# CurrentSens.net
KiCad netlist of a schematic drawn in Altium Designer
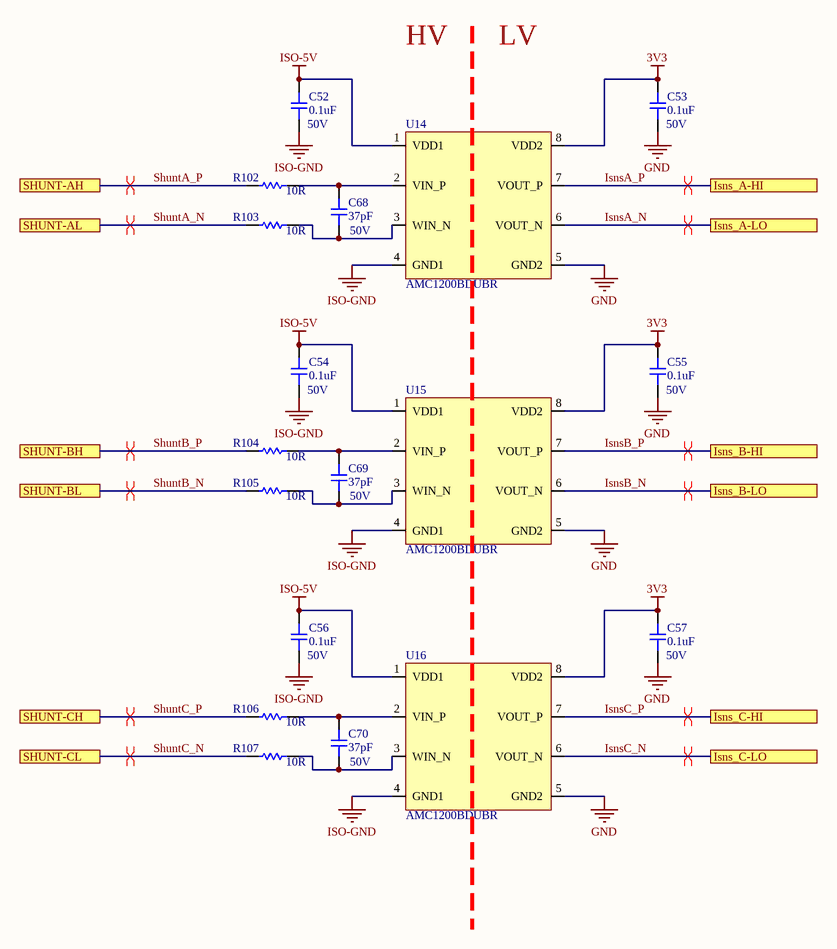
[diagram p0: CurrentSens.SchDoc]

(export (version "E")
  (design (tool "Eeschema 10.0.6"))
  (components
    (comp (ref "C52")
      (value "0.1uF")
      (footprint "CAP-0805")
      (description "CAP CER 0.1UF 50V Y5V 0805")
      (fields
        (field (name "MANUFACTURER") "KEMET")
        (field (name "MANUFACTURER PART NUMBER") "C0805C104Z5VACTU")
        (field (name "VOLTAGE") "50V")
      )
      (libsource (lib "InverterSCHLib") (part "0805-0.1uF-50V"))
    )
    (comp (ref "C53")
      (value "0.1uF")
      (footprint "CAP-0805")
      (description "CAP CER 0.1UF 50V Y5V 0805")
      (fields
        (field (name "MANUFACTURER") "KEMET")
        (field (name "MANUFACTURER PART NUMBER") "C0805C104Z5VACTU")
        (field (name "VOLTAGE") "50V")
      )
      (libsource (lib "InverterSCHLib") (part "0805-0.1uF-50V"))
    )
    (comp (ref "C54")
      (value "0.1uF")
      (footprint "CAP-0805")
      (description "CAP CER 0.1UF 50V Y5V 0805")
      (fields
        (field (name "MANUFACTURER") "KEMET")
        (field (name "MANUFACTURER PART NUMBER") "C0805C104Z5VACTU")
        (field (name "VOLTAGE") "50V")
      )
      (libsource (lib "InverterSCHLib") (part "0805-0.1uF-50V"))
    )
    (comp (ref "C55")
      (value "0.1uF")
      (footprint "CAP-0805")
      (description "CAP CER 0.1UF 50V Y5V 0805")
      (fields
        (field (name "MANUFACTURER") "KEMET")
        (field (name "MANUFACTURER PART NUMBER") "C0805C104Z5VACTU")
        (field (name "VOLTAGE") "50V")
      )
      (libsource (lib "InverterSCHLib") (part "0805-0.1uF-50V"))
    )
    (comp (ref "C56")
      (value "0.1uF")
      (footprint "CAP-0805")
      (description "CAP CER 0.1UF 50V Y5V 0805")
      (fields
        (field (name "MANUFACTURER") "KEMET")
        (field (name "MANUFACTURER PART NUMBER") "C0805C104Z5VACTU")
        (field (name "VOLTAGE RATING") "50V")
      )
      (libsource (lib "InverterSCHLib") (part "0805-0.1uF-50V"))
    )
    (comp (ref "C57")
      (value "0.1uF")
      (footprint "CAP-0805")
      (description "CAP CER 0.1UF 50V Y5V 0805")
      (fields
        (field (name "MANUFACTURER") "KEMET")
        (field (name "MANUFACTURER PART NUMBER") "C0805C104Z5VACTU")
        (field (name "VOLTAGE") "50V")
      )
      (libsource (lib "InverterSCHLib") (part "0805-0.1uF-50V"))
    )
    (comp (ref "C68")
      (value "37pF")
      (footprint "CAP-0805")
      (description "CAP CER 39PF 50V C0G/NP0 0805")
      (fields
        (field (name "MANUFACTURER") "Samsung")
        (field (name "MANUFACTURER PART NUMBER") "CL21C390JBANNNC")
        (field (name "VOLTAGE") "50V")
      )
      (libsource (lib "InverterSCHLib") (part "0805-39pF-50V"))
    )
    (comp (ref "C69")
      (value "37pF")
      (footprint "CAP-0805")
      (description "CAP CER 39PF 50V C0G/NP0 0805")
      (fields
        (field (name "MANUFACTURER") "Samsung")
        (field (name "MANUFACTURER PART NUMBER") "CL21C390JBANNNC")
        (field (name "VOLTAGE") "50V")
      )
      (libsource (lib "InverterSCHLib") (part "0805-39pF-50V"))
    )
    (comp (ref "C70")
      (value "37pF")
      (footprint "CAP-0805")
      (description "CAP CER 39PF 50V C0G/NP0 0805")
      (fields
        (field (name "MANUFACTURER") "Samsung")
        (field (name "MANUFACTURER PART NUMBER") "CL21C390JBANNNC")
        (field (name "VOLTAGE") "50V")
      )
      (libsource (lib "InverterSCHLib") (part "0805-39pF-50V"))
    )
    (comp (ref "R102")
      (value "10R")
      (footprint "RES-0603")
      (description "RES SMD 10 OHM 1% 1/10W 0603")
      (fields
        (field (name "MANUFACTURER") "Yageo")
        (field (name "MANUFACTURER PART NUMBER") "RC0603FR-0710RL")
      )
      (libsource (lib "InverterSCHLib") (part "0603-10R"))
    )
    (comp (ref "R103")
      (value "10R")
      (footprint "RES-0603")
      (description "RES SMD 10 OHM 1% 1/10W 0603")
      (fields
        (field (name "MANUFACTURER") "Yageo")
        (field (name "MANUFACTURER PART NUMBER") "RC0603FR-0710RL")
      )
      (libsource (lib "InverterSCHLib") (part "0603-10R"))
    )
    (comp (ref "R104")
      (value "10R")
      (footprint "RES-0603")
      (description "RES SMD 10 OHM 1% 1/10W 0603")
      (fields
        (field (name "MANUFACTURER") "Yageo")
        (field (name "MANUFACTURER PART NUMBER") "RC0603FR-0710RL")
      )
      (libsource (lib "InverterSCHLib") (part "0603-10R"))
    )
    (comp (ref "R105")
      (value "10R")
      (footprint "RES-0603")
      (description "RES SMD 10 OHM 1% 1/10W 0603")
      (fields
        (field (name "MANUFACTURER") "Yageo")
        (field (name "MANUFACTURER PART NUMBER") "RC0603FR-0710RL")
      )
      (libsource (lib "InverterSCHLib") (part "0603-10R"))
    )
    (comp (ref "R106")
      (value "10R")
      (footprint "RES-0603")
      (description "RES SMD 10 OHM 1% 1/10W 0603")
      (fields
        (field (name "MANUFACTURER") "Yageo")
        (field (name "MANUFACTURER PART NUMBER") "RC0603FR-0710RL")
      )
      (libsource (lib "InverterSCHLib") (part "0603-10R"))
    )
    (comp (ref "R107")
      (value "10R")
      (footprint "RES-0603")
      (description "RES SMD 10 OHM 1% 1/10W 0603")
      (fields
        (field (name "MANUFACTURER") "Yageo")
        (field (name "MANUFACTURER PART NUMBER") "RC0603FR-0710RL")
      )
      (libsource (lib "InverterSCHLib") (part "0603-10R"))
    )
    (comp (ref "U14")
      (value "AMC1200BDUBR")
      (footprint "8-SOP")
      (description "IC OPAMP ISOLATION 1 CIRC 8SOP")
      (fields (field (name "MANUFACTURER") "Texas Instruments"))
      (libsource (lib "InverterSCHLib") (part "ISO-OPAMP"))
    )
    (comp (ref "U15")
      (value "AMC1200BDUBR")
      (footprint "8-SOP")
      (description "IC OPAMP ISOLATION 1 CIRC 8SOP")
      (fields (field (name "MANUFACTURER") "Texas Instruments"))
      (libsource (lib "InverterSCHLib") (part "ISO-OPAMP"))
    )
    (comp (ref "U16")
      (value "AMC1200BDUBR")
      (footprint "8-SOP")
      (description "IC OPAMP ISOLATION 1 CIRC 8SOP")
      (fields (field (name "MANUFACTURER") "Texas Instruments"))
      (libsource (lib "InverterSCHLib") (part "ISO-OPAMP"))
    )
  )
  (nets
    (net (code "1") (name "/IsnsA_N") (class "Default")
      (node (ref "U14") (pin "6") (pinfunction "VOUT_N_6") (pintype "passive"))
    )
    (net (code "2") (name "/IsnsA_P") (class "Default")
      (node (ref "U14") (pin "7") (pinfunction "VOUT_P_7") (pintype "passive"))
    )
    (net (code "3") (name "/IsnsB_N") (class "Default")
      (node (ref "U15") (pin "6") (pinfunction "VOUT_N_6") (pintype "passive"))
    )
    (net (code "4") (name "/IsnsB_P") (class "Default")
      (node (ref "U15") (pin "7") (pinfunction "VOUT_P_7") (pintype "passive"))
    )
    (net (code "5") (name "/IsnsC_N") (class "Default")
      (node (ref "U16") (pin "6") (pinfunction "VOUT_N_6") (pintype "passive"))
    )
    (net (code "6") (name "/IsnsC_P") (class "Default")
      (node (ref "U16") (pin "7") (pinfunction "VOUT_P_7") (pintype "passive"))
    )
    (net (code "7") (name "/ShuntA_N") (class "Default")
      (node (ref "R103") (pin "2") (pinfunction "2_2") (pintype "passive"))
    )
    (net (code "8") (name "/ShuntA_P") (class "Default")
      (node (ref "R102") (pin "2") (pinfunction "2_2") (pintype "passive"))
    )
    (net (code "9") (name "/ShuntB_N") (class "Default")
      (node (ref "R105") (pin "2") (pinfunction "2_2") (pintype "passive"))
    )
    (net (code "10") (name "/ShuntB_P") (class "Default")
      (node (ref "R104") (pin "2") (pinfunction "2_2") (pintype "passive"))
    )
    (net (code "11") (name "/ShuntC_N") (class "Default")
      (node (ref "R107") (pin "2") (pinfunction "2_2") (pintype "passive"))
    )
    (net (code "12") (name "/ShuntC_P") (class "Default")
      (node (ref "R106") (pin "2") (pinfunction "2_2") (pintype "passive"))
    )
    (net (code "13") (name "3V3") (class "Default")
      (node (ref "C53") (pin "2") (pinfunction "2_2") (pintype "passive"))
      (node (ref "C55") (pin "2") (pinfunction "2_2") (pintype "passive"))
      (node (ref "C57") (pin "2") (pinfunction "2_2") (pintype "passive"))
      (node (ref "U14") (pin "8") (pinfunction "VDD2_8") (pintype "passive"))
      (node (ref "U15") (pin "8") (pinfunction "VDD2_8") (pintype "passive"))
      (node (ref "U16") (pin "8") (pinfunction "VDD2_8") (pintype "passive"))
    )
    (net (code "14") (name "GND") (class "Default")
      (node (ref "C53") (pin "1") (pinfunction "1_1") (pintype "passive"))
      (node (ref "C55") (pin "1") (pinfunction "1_1") (pintype "passive"))
      (node (ref "C57") (pin "1") (pinfunction "1_1") (pintype "passive"))
      (node (ref "U14") (pin "5") (pinfunction "GND2_5") (pintype "passive"))
      (node (ref "U15") (pin "5") (pinfunction "GND2_5") (pintype "passive"))
      (node (ref "U16") (pin "5") (pinfunction "GND2_5") (pintype "passive"))
    )
    (net (code "15") (name "ISO-5V") (class "Default")
      (node (ref "C52") (pin "2") (pinfunction "2_2") (pintype "passive"))
      (node (ref "C54") (pin "2") (pinfunction "2_2") (pintype "passive"))
      (node (ref "C56") (pin "2") (pinfunction "2_2") (pintype "passive"))
      (node (ref "U14") (pin "1") (pinfunction "VDD1_1") (pintype "passive"))
      (node (ref "U15") (pin "1") (pinfunction "VDD1_1") (pintype "passive"))
      (node (ref "U16") (pin "1") (pinfunction "VDD1_1") (pintype "passive"))
    )
    (net (code "16") (name "ISO-GND") (class "Default")
      (node (ref "C52") (pin "1") (pinfunction "1_1") (pintype "passive"))
      (node (ref "C54") (pin "1") (pinfunction "1_1") (pintype "passive"))
      (node (ref "C56") (pin "1") (pinfunction "1_1") (pintype "passive"))
      (node (ref "U14") (pin "4") (pinfunction "GND1_4") (pintype "passive"))
      (node (ref "U15") (pin "4") (pinfunction "GND1_4") (pintype "passive"))
      (node (ref "U16") (pin "4") (pinfunction "GND1_4") (pintype "passive"))
    )
    (net (code "17") (name "Net-(U14-VIN_P)") (class "Default")
      (node (ref "C68") (pin "2") (pinfunction "2_2") (pintype "passive"))
      (node (ref "R102") (pin "1") (pinfunction "1_1") (pintype "passive"))
      (node (ref "U14") (pin "2") (pinfunction "VIN_P_2") (pintype "passive"))
    )
    (net (code "18") (name "Net-(U14-WIN_N)") (class "Default")
      (node (ref "C68") (pin "1") (pinfunction "1_1") (pintype "passive"))
      (node (ref "R103") (pin "1") (pinfunction "1_1") (pintype "passive"))
      (node (ref "U14") (pin "3") (pinfunction "WIN_N_3") (pintype "passive"))
    )
    (net (code "19") (name "Net-(U15-VIN_P)") (class "Default")
      (node (ref "C69") (pin "2") (pinfunction "2_2") (pintype "passive"))
      (node (ref "R104") (pin "1") (pinfunction "1_1") (pintype "passive"))
      (node (ref "U15") (pin "2") (pinfunction "VIN_P_2") (pintype "passive"))
    )
    (net (code "20") (name "Net-(U15-WIN_N)") (class "Default")
      (node (ref "C69") (pin "1") (pinfunction "1_1") (pintype "passive"))
      (node (ref "R105") (pin "1") (pinfunction "1_1") (pintype "passive"))
      (node (ref "U15") (pin "3") (pinfunction "WIN_N_3") (pintype "passive"))
    )
    (net (code "21") (name "Net-(U16-VIN_P)") (class "Default")
      (node (ref "C70") (pin "2") (pinfunction "2_2") (pintype "passive"))
      (node (ref "R106") (pin "1") (pinfunction "1_1") (pintype "passive"))
      (node (ref "U16") (pin "2") (pinfunction "VIN_P_2") (pintype "passive"))
    )
    (net (code "22") (name "Net-(U16-WIN_N)") (class "Default")
      (node (ref "C70") (pin "1") (pinfunction "1_1") (pintype "passive"))
      (node (ref "R107") (pin "1") (pinfunction "1_1") (pintype "passive"))
      (node (ref "U16") (pin "3") (pinfunction "WIN_N_3") (pintype "passive"))
    )
  )
)
